# LCD-24.net
KiCad netlist of a schematic drawn in Altium Designer
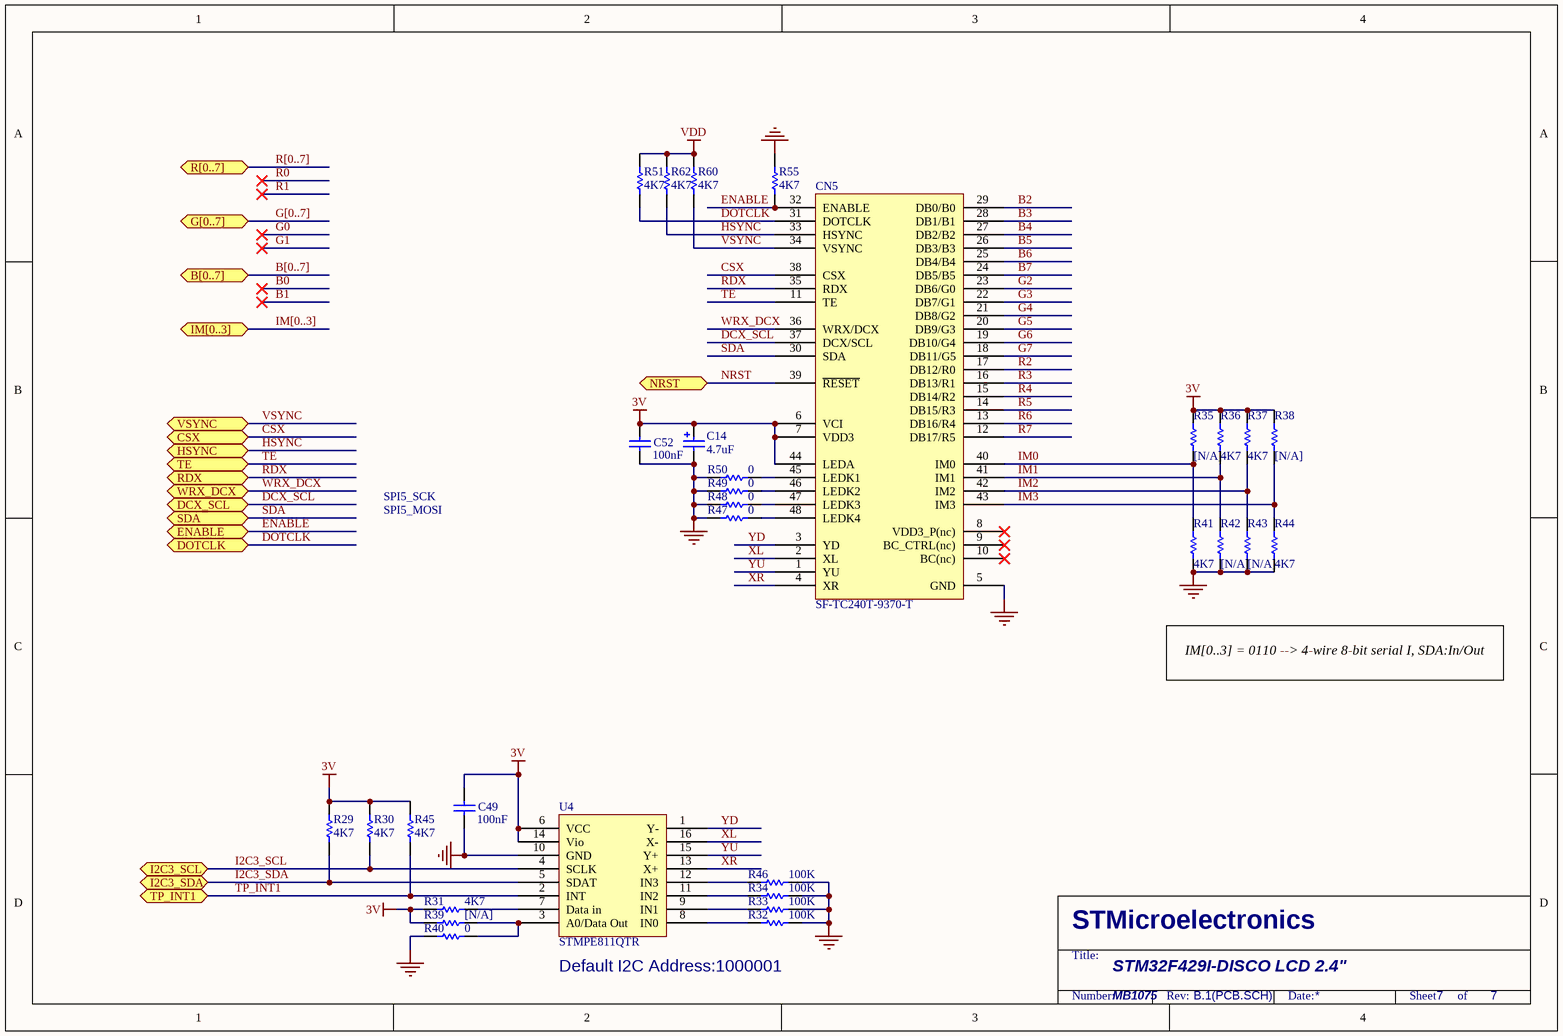
[diagram p0: LCD-24.SchDoc]

(export (version "E")
  (design (tool "Eeschema 10.0.6"))
  (components
    (comp (ref "C14")
      (value "4.7uF")
      (footprint "TAN-A")
      (description "Polarized Capacitor (Radial)")
      (fields (field (name "PUBLISHER") "Altium Limited"))
      (libsource (lib "Miscellaneous Devices") (part "Cap Pol1"))
    )
    (comp (ref "C49")
      (value "100nF")
      (footprint "0402C")
      (description "Capacitor 0402 / 0603 / 0805")
      (libsource (lib "MCD_TOOLS") (part "Capacitor_ST"))
    )
    (comp (ref "C52")
      (value "100nF")
      (footprint "0402C")
      (description "Capacitor 0402 / 0603 / 0805")
      (libsource (lib "MCD_TOOLS") (part "Capacitor_ST"))
    )
    (comp (ref "CN5")
      (value "SF-TC240T-9370-T")
      (footprint "SF-TC240T-48P-07")
      (description "2.4\" LCD TFT 320x240 with Touch Panel")
      (libsource (lib "MCD_TOOLS") (part "SF-TC240T-9370-T"))
    )
    (comp (ref "R29")
      (value "4K7")
      (footprint "0402R")
      (description "Resistor 0402 or 0603 or 0805")
      (libsource (lib "MCD_TOOLS") (part "Resistor_ST"))
    )
    (comp (ref "R30")
      (value "4K7")
      (footprint "0402R")
      (description "Resistor 0402 or 0603 or 0805")
      (libsource (lib "MCD_TOOLS") (part "Resistor_ST"))
    )
    (comp (ref "R31")
      (value "4K7")
      (footprint "0402R")
      (description "Resistor 0402 or 0603 or 0805")
      (libsource (lib "MCD_TOOLS") (part "Resistor_ST"))
    )
    (comp (ref "R32")
      (value "100K")
      (footprint "0402R")
      (description "Resistor 0402 or 0603 or 0805")
      (libsource (lib "MCD_TOOLS") (part "Resistor_ST"))
    )
    (comp (ref "R33")
      (value "100K")
      (footprint "0402R")
      (description "Resistor 0402 or 0603 or 0805")
      (libsource (lib "MCD_TOOLS") (part "Resistor_ST"))
    )
    (comp (ref "R34")
      (value "100K")
      (footprint "0402R")
      (description "Resistor 0402 or 0603 or 0805")
      (libsource (lib "MCD_TOOLS") (part "Resistor_ST"))
    )
    (comp (ref "R35")
      (value "[N/A]")
      (footprint "0402R")
      (description "Resistor 0402 or 0603 or 0805")
      (libsource (lib "MCD_TOOLS") (part "Resistor_ST"))
    )
    (comp (ref "R36")
      (value "4K7")
      (footprint "0402R")
      (description "Resistor 0402 or 0603 or 0805")
      (libsource (lib "MCD_TOOLS") (part "Resistor_ST"))
    )
    (comp (ref "R37")
      (value "4K7")
      (footprint "0402R")
      (description "Resistor 0402 or 0603 or 0805")
      (libsource (lib "MCD_TOOLS") (part "Resistor_ST"))
    )
    (comp (ref "R38")
      (value "[N/A]")
      (footprint "0402R")
      (description "Resistor 0402 or 0603 or 0805")
      (libsource (lib "MCD_TOOLS") (part "Resistor_ST"))
    )
    (comp (ref "R39")
      (value "[N/A]")
      (footprint "0402R")
      (description "Resistor 0402 or 0603 or 0805")
      (libsource (lib "MCD_TOOLS") (part "Resistor_ST"))
    )
    (comp (ref "R40")
      (value "0")
      (footprint "0402R")
      (description "Resistor 0402 or 0603 or 0805")
      (libsource (lib "MCD_TOOLS") (part "Resistor_ST"))
    )
    (comp (ref "R41")
      (value "4K7")
      (footprint "0402R")
      (description "Resistor 0402 or 0603 or 0805")
      (libsource (lib "MCD_TOOLS") (part "Resistor_ST"))
    )
    (comp (ref "R42")
      (value "[N/A]")
      (footprint "0402R")
      (description "Resistor 0402 or 0603 or 0805")
      (libsource (lib "MCD_TOOLS") (part "Resistor_ST"))
    )
    (comp (ref "R43")
      (value "[N/A]")
      (footprint "0402R")
      (description "Resistor 0402 or 0603 or 0805")
      (libsource (lib "MCD_TOOLS") (part "Resistor_ST"))
    )
    (comp (ref "R44")
      (value "4K7")
      (footprint "0402R")
      (description "Resistor 0402 or 0603 or 0805")
      (libsource (lib "MCD_TOOLS") (part "Resistor_ST"))
    )
    (comp (ref "R45")
      (value "4K7")
      (footprint "0402R")
      (description "Resistor 0402 or 0603 or 0805")
      (libsource (lib "MCD_TOOLS") (part "Resistor_ST"))
    )
    (comp (ref "R46")
      (value "100K")
      (footprint "0402R")
      (description "Resistor 0402 or 0603 or 0805")
      (libsource (lib "MCD_TOOLS") (part "Resistor_ST"))
    )
    (comp (ref "R47")
      (value "0")
      (footprint "0603R")
      (description "Resistor 0402 or 0603 or 0805")
      (libsource (lib "MCD_TOOLS") (part "Resistor_ST"))
    )
    (comp (ref "R48")
      (value "0")
      (footprint "0603R")
      (description "Resistor 0402 or 0603 or 0805")
      (libsource (lib "MCD_TOOLS") (part "Resistor_ST"))
    )
    (comp (ref "R49")
      (value "0")
      (footprint "0603R")
      (description "Resistor 0402 or 0603 or 0805")
      (libsource (lib "MCD_TOOLS") (part "Resistor_ST"))
    )
    (comp (ref "R50")
      (value "0")
      (footprint "0603R")
      (description "Resistor 0402 or 0603 or 0805")
      (libsource (lib "MCD_TOOLS") (part "Resistor_ST"))
    )
    (comp (ref "R51")
      (value "4K7")
      (footprint "0402R")
      (description "Resistor 0402 or 0603 or 0805")
      (libsource (lib "MCD_TOOLS") (part "Resistor_ST"))
    )
    (comp (ref "R55")
      (value "4K7")
      (footprint "0402R")
      (description "Resistor 0402 or 0603 or 0805")
      (libsource (lib "MCD_TOOLS") (part "Resistor_ST"))
    )
    (comp (ref "R60")
      (value "4K7")
      (footprint "0402R")
      (description "Resistor 0402 or 0603 or 0805")
      (libsource (lib "MCD_TOOLS") (part "Resistor_ST"))
    )
    (comp (ref "R62")
      (value "4K7")
      (footprint "0402R")
      (description "Resistor 0402 or 0603 or 0805")
      (libsource (lib "MCD_TOOLS") (part "Resistor_ST"))
    )
    (comp (ref "U4")
      (value "STMPE811QTR")
      (footprint "QFN16_3X3")
      (description "S-Touch® advanced resistive touchscreen controller, with 8-bit GPIO expander")
      (libsource (lib "MCD_TOOLS") (part "STMPE811"))
    )
  )
  (nets
    (net (code "3") (name "/B2") (class "Default")
      (node (ref "CN5") (pin "29") (pinfunction "DB0/B0_29") (pintype "passive"))
    )
    (net (code "4") (name "/B3") (class "Default")
      (node (ref "CN5") (pin "28") (pinfunction "DB1/B1_28") (pintype "passive"))
    )
    (net (code "5") (name "/B4") (class "Default")
      (node (ref "CN5") (pin "27") (pinfunction "DB2/B2_27") (pintype "passive"))
    )
    (net (code "6") (name "/B5") (class "Default")
      (node (ref "CN5") (pin "26") (pinfunction "DB3/B3_26") (pintype "passive"))
    )
    (net (code "7") (name "/B6") (class "Default")
      (node (ref "CN5") (pin "25") (pinfunction "DB4/B4_25") (pintype "passive"))
    )
    (net (code "8") (name "/B7") (class "Default")
      (node (ref "CN5") (pin "24") (pinfunction "DB5/B5_24") (pintype "passive"))
    )
    (net (code "10") (name "/CSX") (class "Default")
      (node (ref "CN5") (pin "38") (pinfunction "CSX_38") (pintype "passive"))
    )
    (net (code "11") (name "/DCX_SCL") (class "Default")
      (node (ref "CN5") (pin "37") (pinfunction "DCX/SCL_37") (pintype "passive"))
    )
    (net (code "12") (name "/DOTCLK") (class "Default")
      (node (ref "CN5") (pin "31") (pinfunction "DOTCLK_31") (pintype "passive"))
      (node (ref "R51") (pin "1") (pinfunction "1_1") (pintype "passive"))
    )
    (net (code "13") (name "/ENABLE") (class "Default")
      (node (ref "CN5") (pin "32") (pinfunction "ENABLE_32") (pintype "passive"))
      (node (ref "R55") (pin "1") (pinfunction "1_1") (pintype "passive"))
    )
    (net (code "16") (name "/G2") (class "Default")
      (node (ref "CN5") (pin "23") (pinfunction "DB6/G0_23") (pintype "passive"))
    )
    (net (code "17") (name "/G3") (class "Default")
      (node (ref "CN5") (pin "22") (pinfunction "DB7/G1_22") (pintype "passive"))
    )
    (net (code "18") (name "/G4") (class "Default")
      (node (ref "CN5") (pin "21") (pinfunction "DB8/G2_21") (pintype "passive"))
    )
    (net (code "19") (name "/G5") (class "Default")
      (node (ref "CN5") (pin "20") (pinfunction "DB9/G3_20") (pintype "passive"))
    )
    (net (code "20") (name "/G6") (class "Default")
      (node (ref "CN5") (pin "19") (pinfunction "DB10/G4_19") (pintype "passive"))
    )
    (net (code "21") (name "/G7") (class "Default")
      (node (ref "CN5") (pin "18") (pinfunction "DB11/G5_18") (pintype "passive"))
    )
    (net (code "23") (name "/HSYNC") (class "Default")
      (node (ref "CN5") (pin "33") (pinfunction "HSYNC_33") (pintype "passive"))
      (node (ref "R62") (pin "1") (pinfunction "1_1") (pintype "passive"))
    )
    (net (code "24") (name "/I2C3_SCL") (class "Default")
      (node (ref "R30") (pin "1") (pinfunction "1_1") (pintype "passive"))
      (node (ref "U4") (pin "4") (pinfunction "SCLK_4") (pintype "passive"))
    )
    (net (code "25") (name "/I2C3_SDA") (class "Default")
      (node (ref "R29") (pin "1") (pinfunction "1_1") (pintype "passive"))
      (node (ref "U4") (pin "5") (pinfunction "SDAT_5") (pintype "passive"))
    )
    (net (code "26") (name "/IM0") (class "Default")
      (node (ref "CN5") (pin "40") (pinfunction "IM0_40") (pintype "passive"))
      (node (ref "R35") (pin "1") (pinfunction "1_1") (pintype "passive"))
      (node (ref "R41") (pin "2") (pinfunction "2_2") (pintype "passive"))
    )
    (net (code "27") (name "/IM1") (class "Default")
      (node (ref "CN5") (pin "41") (pinfunction "IM1_41") (pintype "passive"))
      (node (ref "R36") (pin "1") (pinfunction "1_1") (pintype "passive"))
      (node (ref "R42") (pin "2") (pinfunction "2_2") (pintype "passive"))
    )
    (net (code "28") (name "/IM2") (class "Default")
      (node (ref "CN5") (pin "42") (pinfunction "IM2_42") (pintype "passive"))
      (node (ref "R37") (pin "1") (pinfunction "1_1") (pintype "passive"))
      (node (ref "R43") (pin "2") (pinfunction "2_2") (pintype "passive"))
    )
    (net (code "29") (name "/IM3") (class "Default")
      (node (ref "CN5") (pin "43") (pinfunction "IM3_43") (pintype "passive"))
      (node (ref "R38") (pin "1") (pinfunction "1_1") (pintype "passive"))
      (node (ref "R44") (pin "2") (pinfunction "2_2") (pintype "passive"))
    )
    (net (code "31") (name "/NRST") (class "Default")
      (node (ref "CN5") (pin "39") (pinfunction "~{RESET}_39") (pintype "passive"))
    )
    (net (code "34") (name "/R2") (class "Default")
      (node (ref "CN5") (pin "17") (pinfunction "DB12/R0_17") (pintype "passive"))
    )
    (net (code "35") (name "/R3") (class "Default")
      (node (ref "CN5") (pin "16") (pinfunction "DB13/R1_16") (pintype "passive"))
    )
    (net (code "36") (name "/R4") (class "Default")
      (node (ref "CN5") (pin "15") (pinfunction "DB14/R2_15") (pintype "passive"))
    )
    (net (code "37") (name "/R5") (class "Default")
      (node (ref "CN5") (pin "14") (pinfunction "DB15/R3_14") (pintype "passive"))
    )
    (net (code "38") (name "/R6") (class "Default")
      (node (ref "CN5") (pin "13") (pinfunction "DB16/R4_13") (pintype "passive"))
    )
    (net (code "39") (name "/R7") (class "Default")
      (node (ref "CN5") (pin "12") (pinfunction "DB17/R5_12") (pintype "passive"))
    )
    (net (code "40") (name "/RDX") (class "Default")
      (node (ref "CN5") (pin "35") (pinfunction "RDX_35") (pintype "passive"))
    )
    (net (code "42") (name "/SDA") (class "Default")
      (node (ref "CN5") (pin "30") (pinfunction "SDA_30") (pintype "passive"))
    )
    (net (code "43") (name "/TE") (class "Default")
      (node (ref "CN5") (pin "11") (pinfunction "TE_11") (pintype "passive"))
    )
    (net (code "44") (name "/TP_INT1") (class "Default")
      (node (ref "R45") (pin "1") (pinfunction "1_1") (pintype "passive"))
      (node (ref "U4") (pin "2") (pinfunction "INT_2") (pintype "passive"))
    )
    (net (code "45") (name "/VSYNC") (class "Default")
      (node (ref "CN5") (pin "34") (pinfunction "VSYNC_34") (pintype "passive"))
      (node (ref "R60") (pin "1") (pinfunction "1_1") (pintype "passive"))
    )
    (net (code "46") (name "/WRX_DCX") (class "Default")
      (node (ref "CN5") (pin "36") (pinfunction "WRX/DCX_36") (pintype "passive"))
    )
    (net (code "47") (name "/XL") (class "Default")
      (node (ref "CN5") (pin "2") (pinfunction "XL_2") (pintype "passive"))
      (node (ref "U4") (pin "16") (pinfunction "X-_16") (pintype "passive"))
    )
    (net (code "48") (name "/XR") (class "Default")
      (node (ref "CN5") (pin "4") (pinfunction "XR_4") (pintype "passive"))
      (node (ref "U4") (pin "13") (pinfunction "X+_13") (pintype "passive"))
    )
    (net (code "49") (name "/YD") (class "Default")
      (node (ref "CN5") (pin "3") (pinfunction "YD_3") (pintype "passive"))
      (node (ref "U4") (pin "1") (pinfunction "Y-_1") (pintype "passive"))
    )
    (net (code "50") (name "/YU") (class "Default")
      (node (ref "CN5") (pin "1") (pinfunction "YU_1") (pintype "passive"))
      (node (ref "U4") (pin "15") (pinfunction "Y+_15") (pintype "passive"))
    )
    (net (code "51") (name "3V") (class "Default")
      (node (ref "C14") (pin "1") (pinfunction "1_1") (pintype "passive"))
      (node (ref "C49") (pin "2") (pinfunction "2_2") (pintype "passive"))
      (node (ref "C52") (pin "2") (pinfunction "2_2") (pintype "passive"))
      (node (ref "CN5") (pin "44") (pinfunction "LEDA_44") (pintype "passive"))
      (node (ref "CN5") (pin "6") (pinfunction "VCI_6") (pintype "passive"))
      (node (ref "CN5") (pin "7") (pinfunction "VDD3_7") (pintype "passive"))
      (node (ref "R29") (pin "2") (pinfunction "2_2") (pintype "passive"))
      (node (ref "R30") (pin "2") (pinfunction "2_2") (pintype "passive"))
      (node (ref "R31") (pin "1") (pinfunction "1_1") (pintype "passive"))
      (node (ref "R35") (pin "2") (pinfunction "2_2") (pintype "passive"))
      (node (ref "R36") (pin "2") (pinfunction "2_2") (pintype "passive"))
      (node (ref "R37") (pin "2") (pinfunction "2_2") (pintype "passive"))
      (node (ref "R38") (pin "2") (pinfunction "2_2") (pintype "passive"))
      (node (ref "R39") (pin "1") (pinfunction "1_1") (pintype "passive"))
      (node (ref "R45") (pin "2") (pinfunction "2_2") (pintype "passive"))
      (node (ref "U4") (pin "14") (pinfunction "Vio_14") (pintype "passive"))
      (node (ref "U4") (pin "6") (pinfunction "VCC_6") (pintype "passive"))
    )
    (net (code "52") (name "GND") (class "Default")
      (node (ref "C14") (pin "2") (pinfunction "2_2") (pintype "passive"))
      (node (ref "C49") (pin "1") (pinfunction "1_1") (pintype "passive"))
      (node (ref "C52") (pin "1") (pinfunction "1_1") (pintype "passive"))
      (node (ref "CN5") (pin "5") (pinfunction "GND_5") (pintype "passive"))
      (node (ref "R32") (pin "2") (pinfunction "2_2") (pintype "passive"))
      (node (ref "R33") (pin "2") (pinfunction "2_2") (pintype "passive"))
      (node (ref "R34") (pin "2") (pinfunction "2_2") (pintype "passive"))
      (node (ref "R40") (pin "1") (pinfunction "1_1") (pintype "passive"))
      (node (ref "R41") (pin "1") (pinfunction "1_1") (pintype "passive"))
      (node (ref "R42") (pin "1") (pinfunction "1_1") (pintype "passive"))
      (node (ref "R43") (pin "1") (pinfunction "1_1") (pintype "passive"))
      (node (ref "R44") (pin "1") (pinfunction "1_1") (pintype "passive"))
      (node (ref "R46") (pin "2") (pinfunction "2_2") (pintype "passive"))
      (node (ref "R47") (pin "1") (pinfunction "1_1") (pintype "passive"))
      (node (ref "R48") (pin "1") (pinfunction "1_1") (pintype "passive"))
      (node (ref "R49") (pin "1") (pinfunction "1_1") (pintype "passive"))
      (node (ref "R50") (pin "1") (pinfunction "1_1") (pintype "passive"))
      (node (ref "R55") (pin "2") (pinfunction "2_2") (pintype "passive"))
      (node (ref "U4") (pin "10") (pinfunction "GND_10") (pintype "passive"))
    )
    (net (code "53") (name "Net-(CN5-LEDK1)") (class "Default")
      (node (ref "CN5") (pin "45") (pinfunction "LEDK1_45") (pintype "passive"))
      (node (ref "R50") (pin "2") (pinfunction "2_2") (pintype "passive"))
    )
    (net (code "54") (name "Net-(CN5-LEDK2)") (class "Default")
      (node (ref "CN5") (pin "46") (pinfunction "LEDK2_46") (pintype "passive"))
      (node (ref "R49") (pin "2") (pinfunction "2_2") (pintype "passive"))
    )
    (net (code "55") (name "Net-(CN5-LEDK3)") (class "Default")
      (node (ref "CN5") (pin "47") (pinfunction "LEDK3_47") (pintype "passive"))
      (node (ref "R48") (pin "2") (pinfunction "2_2") (pintype "passive"))
    )
    (net (code "56") (name "Net-(CN5-LEDK4)") (class "Default")
      (node (ref "CN5") (pin "48") (pinfunction "LEDK4_48") (pintype "passive"))
      (node (ref "R47") (pin "2") (pinfunction "2_2") (pintype "passive"))
    )
    (net (code "57") (name "Net-(U4-A0{slash}Data_Out)") (class "Default")
      (node (ref "R39") (pin "2") (pinfunction "2_2") (pintype "passive"))
      (node (ref "R40") (pin "2") (pinfunction "2_2") (pintype "passive"))
      (node (ref "U4") (pin "3") (pinfunction "A0/Data_Out_3") (pintype "passive"))
    )
    (net (code "58") (name "Net-(U4-Data_in)") (class "Default")
      (node (ref "R31") (pin "2") (pinfunction "2_2") (pintype "passive"))
      (node (ref "U4") (pin "7") (pinfunction "Data_in_7") (pintype "passive"))
    )
    (net (code "59") (name "Net-(U4-IN0)") (class "Default")
      (node (ref "R32") (pin "1") (pinfunction "1_1") (pintype "passive"))
      (node (ref "U4") (pin "8") (pinfunction "IN0_8") (pintype "passive"))
    )
    (net (code "60") (name "Net-(U4-IN1)") (class "Default")
      (node (ref "R33") (pin "1") (pinfunction "1_1") (pintype "passive"))
      (node (ref "U4") (pin "9") (pinfunction "IN1_9") (pintype "passive"))
    )
    (net (code "61") (name "Net-(U4-IN2)") (class "Default")
      (node (ref "R34") (pin "1") (pinfunction "1_1") (pintype "passive"))
      (node (ref "U4") (pin "11") (pinfunction "IN2_11") (pintype "passive"))
    )
    (net (code "62") (name "Net-(U4-IN3)") (class "Default")
      (node (ref "R46") (pin "1") (pinfunction "1_1") (pintype "passive"))
      (node (ref "U4") (pin "12") (pinfunction "IN3_12") (pintype "passive"))
    )
    (net (code "63") (name "VDD") (class "Default")
      (node (ref "R51") (pin "2") (pinfunction "2_2") (pintype "passive"))
      (node (ref "R60") (pin "2") (pinfunction "2_2") (pintype "passive"))
      (node (ref "R62") (pin "2") (pinfunction "2_2") (pintype "passive"))
    )
    (net (code "64") (name "unconnected-(CN5-BC(nc)-Pad10)") (class "Default")
      (node (ref "CN5") (pin "10") (pinfunction "BC(nc)_10") (pintype "passive+no_connect"))
    )
    (net (code "65") (name "unconnected-(CN5-BC_CTRL(nc)-Pad9)") (class "Default")
      (node (ref "CN5") (pin "9") (pinfunction "BC_CTRL(nc)_9") (pintype "passive+no_connect"))
    )
    (net (code "66") (name "unconnected-(CN5-VDD3_P(nc)-Pad8)") (class "Default")
      (node (ref "CN5") (pin "8") (pinfunction "VDD3_P(nc)_8") (pintype "passive+no_connect"))
    )
  )
)
